# PSU_VCC2V5_Buck.net
KiCad netlist of a schematic drawn in Altium Designer
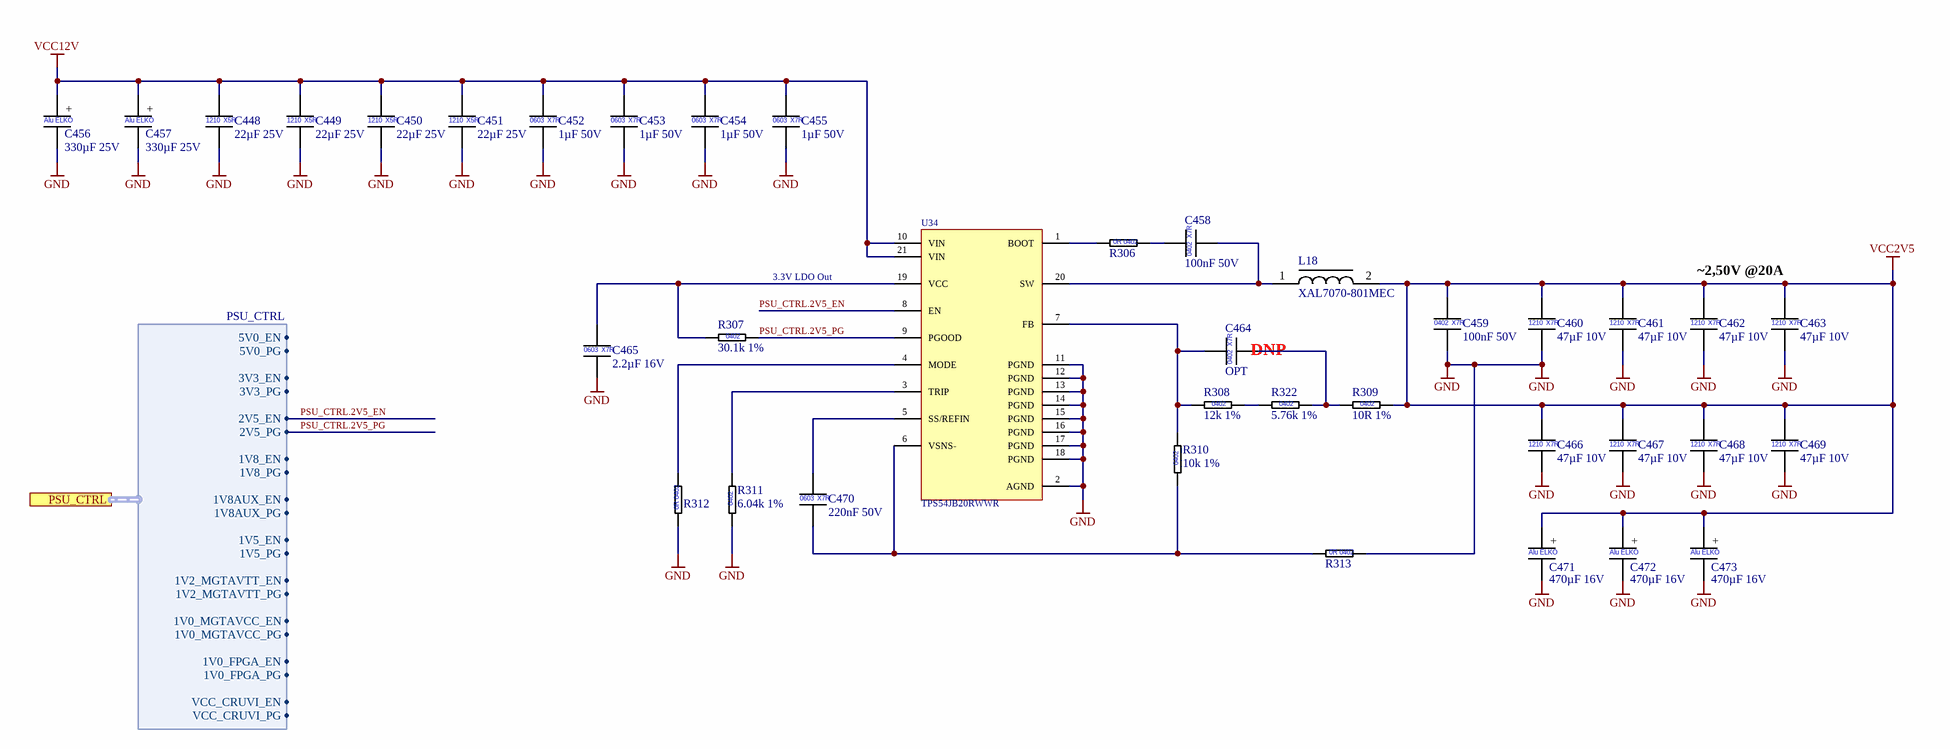
[diagram p0: PSU_VCC2V5_Buck.SchDoc]

(export (version "E")
  (design (tool "Eeschema 10.0.6"))
  (components
    (comp (ref "C448")
      (value "22µF 25V")
      (footprint "Cap:CAP_1210")
      (description "Multilayer Ceramic Capacitors MLCC - SMD/SMT 1210 25VDC")
      (libsource (lib "Cap") (part "CAP_1210_22µF_25V"))
    )
    (comp (ref "C449")
      (value "22µF 25V")
      (footprint "Cap:CAP_1210")
      (description "Multilayer Ceramic Capacitors MLCC - SMD/SMT 1210 25VDC")
      (libsource (lib "Cap") (part "CAP_1210_22µF_25V"))
    )
    (comp (ref "C450")
      (value "22µF 25V")
      (footprint "Cap:CAP_1210")
      (description "Multilayer Ceramic Capacitors MLCC - SMD/SMT 1210 25VDC")
      (libsource (lib "Cap") (part "CAP_1210_22µF_25V"))
    )
    (comp (ref "C451")
      (value "22µF 25V")
      (footprint "Cap:CAP_1210")
      (description "Multilayer Ceramic Capacitors MLCC - SMD/SMT 1210 25VDC")
      (libsource (lib "Cap") (part "CAP_1210_22µF_25V"))
    )
    (comp (ref "C452")
      (value "1µF 50V")
      (footprint "CAP_0603")
      (description "Multilayer Ceramic Capacitors MLCC - SMD/SMT 50V 1uF X7R 0603 10%")
      (libsource (lib "Cap") (part "CAP_0603_1µF_50V_X7R_10%"))
    )
    (comp (ref "C453")
      (value "1µF 50V")
      (footprint "CAP_0603")
      (description "Multilayer Ceramic Capacitors MLCC - SMD/SMT 50V 1uF X7R 0603 10%")
      (libsource (lib "Cap") (part "CAP_0603_1µF_50V_X7R_10%"))
    )
    (comp (ref "C454")
      (value "1µF 50V")
      (footprint "CAP_0603")
      (description "Multilayer Ceramic Capacitors MLCC - SMD/SMT 50V 1uF X7R 0603 10%")
      (libsource (lib "Cap") (part "CAP_0603_1µF_50V_X7R_10%"))
    )
    (comp (ref "C455")
      (value "1µF 50V")
      (footprint "CAP_0603")
      (description "Multilayer Ceramic Capacitors MLCC - SMD/SMT 50V 1uF X7R 0603 10%")
      (libsource (lib "Cap") (part "CAP_0603_1µF_50V_X7R_10%"))
    )
    (comp (ref "C456")
      (value "330µF 25V")
      (footprint "Cap:WCAP-PTG5_D10H12.5")
      (description "Organische Polymer-Aluminiumkondensatoren 330uF 25 Volts 20% AEC-Q200")
      (libsource (lib "Cap") (part "CAP_D10L12.5_330µF_25V"))
    )
    (comp (ref "C457")
      (value "330µF 25V")
      (footprint "Cap:WCAP-PTG5_D10H12.5")
      (description "Organische Polymer-Aluminiumkondensatoren 330uF 25 Volts 20% AEC-Q200")
      (libsource (lib "Cap") (part "CAP_D10L12.5_330µF_25V"))
    )
    (comp (ref "C458")
      (value "100nF 50V")
      (footprint "Cap:CAP_0402")
      (description "Multilayer Ceramic Capacitors MLCC - SMD/SMT 0402 50VDC")
      (libsource (lib "") (part "CAP_0402_100nF_50V_1"))
    )
    (comp (ref "C459")
      (value "100nF 50V")
      (footprint "Cap:CAP_0402")
      (description "Multilayer Ceramic Capacitors MLCC - SMD/SMT 0402 50VDC")
      (libsource (lib "Cap") (part "CAP_0402_100nF_50V"))
    )
    (comp (ref "C460")
      (value "47µF 10V")
      (footprint "Cap:CAP_1210")
      (description "Multilayer Ceramic Capacitors MLCC - SMD/SMT 47 uF 10 VDC 10% 1210 X7R")
      (libsource (lib "Cap") (part "CAP_1210_47µF_10V_X7R_10%"))
    )
    (comp (ref "C461")
      (value "47µF 10V")
      (footprint "Cap:CAP_1210")
      (description "Multilayer Ceramic Capacitors MLCC - SMD/SMT 47 uF 10 VDC 10% 1210 X7R")
      (libsource (lib "Cap") (part "CAP_1210_47µF_10V_X7R_10%"))
    )
    (comp (ref "C462")
      (value "47µF 10V")
      (footprint "Cap:CAP_1210")
      (description "Multilayer Ceramic Capacitors MLCC - SMD/SMT 47 uF 10 VDC 10% 1210 X7R")
      (libsource (lib "Cap") (part "CAP_1210_47µF_10V_X7R_10%"))
    )
    (comp (ref "C463")
      (value "47µF 10V")
      (footprint "Cap:CAP_1210")
      (description "Multilayer Ceramic Capacitors MLCC - SMD/SMT 47 uF 10 VDC 10% 1210 X7R")
      (libsource (lib "Cap") (part "CAP_1210_47µF_10V_X7R_10%"))
    )
    (comp (ref "C464")
      (value "OPT")
      (footprint "Cap:CAP_0402")
      (description "Multilayer Ceramic Capacitors MLCC - SMD/SMT 0402 Optional Placeholder")
      (libsource (lib "Cap") (part "CAP_0402_OPT"))
    )
    (comp (ref "C465")
      (value "2.2µF 16V")
      (footprint "Cap:CAP_0603")
      (description "Multilayer Ceramic Capacitors MLCC - SMD/SMT 2.2 uF 16 VDC 10% 0603 X7R")
      (libsource (lib "Cap") (part "CAP_0603_2.2µF_16V_X7R_10%"))
    )
    (comp (ref "C466")
      (value "47µF 10V")
      (footprint "Cap:CAP_1210")
      (description "Multilayer Ceramic Capacitors MLCC - SMD/SMT 47 uF 10 VDC 10% 1210 X7R")
      (libsource (lib "Cap") (part "CAP_1210_47µF_10V_X7R_10%"))
    )
    (comp (ref "C467")
      (value "47µF 10V")
      (footprint "Cap:CAP_1210")
      (description "Multilayer Ceramic Capacitors MLCC - SMD/SMT 47 uF 10 VDC 10% 1210 X7R")
      (libsource (lib "Cap") (part "CAP_1210_47µF_10V_X7R_10%"))
    )
    (comp (ref "C468")
      (value "47µF 10V")
      (footprint "Cap:CAP_1210")
      (description "Multilayer Ceramic Capacitors MLCC - SMD/SMT 47 uF 10 VDC 10% 1210 X7R")
      (libsource (lib "Cap") (part "CAP_1210_47µF_10V_X7R_10%"))
    )
    (comp (ref "C469")
      (value "47µF 10V")
      (footprint "Cap:CAP_1210")
      (description "Multilayer Ceramic Capacitors MLCC - SMD/SMT 47 uF 10 VDC 10% 1210 X7R")
      (libsource (lib "Cap") (part "CAP_1210_47µF_10V_X7R_10%"))
    )
    (comp (ref "C470")
      (value "220nF 50V")
      (footprint "CAP_0603")
      (description "Multilayer Ceramic Capacitors MLCC - SMD/SMT 0.22 uF 50 VDC 10% 0603 X7R")
      (libsource (lib "Cap") (part "CAP_0603_220nF_50V_X7R_10%"))
    )
    (comp (ref "C471")
      (value "470µF 16V")
      (footprint "Cap:WCAP-PTG5_D8H13")
      (description "Organische Polymer-Aluminiumkondensatoren 470uF 16 Volts 20%")
      (libsource (lib "Cap") (part "CAP_D8L9_470µF_16V"))
    )
    (comp (ref "C472")
      (value "470µF 16V")
      (footprint "Cap:WCAP-PTG5_D8H13")
      (description "Organische Polymer-Aluminiumkondensatoren 470uF 16 Volts 20%")
      (libsource (lib "Cap") (part "CAP_D8L9_470µF_16V"))
    )
    (comp (ref "C473")
      (value "470µF 16V")
      (footprint "Cap:WCAP-PTG5_D8H13")
      (description "Organische Polymer-Aluminiumkondensatoren 470uF 16 Volts 20%")
      (libsource (lib "Cap") (part "CAP_D8L9_470µF_16V"))
    )
    (comp (ref "L18")
      (value "XAL7070-801MEC")
      (footprint "indc:COILCRAFT_XAL7070")
      (description "Power Inductors - SMD 800nH Shld 20% 25.8A 2.29mOhms AECQ200")
      (libsource (lib "Indc") (part "XAL7070-801MEC_Power Inductors SMD 800nH Shld 20% 25.8A 2.29mOhms AECQ200"))
    )
    (comp (ref "R306")
      (value "0R Jumper")
      (footprint "res:RES_0402")
      (description "Thick Film Resistors - SMD 0Ohm")
      (libsource (lib "Res") (part "RES_0402_0R Jumper"))
    )
    (comp (ref "R307")
      (value "30.1k 1%")
      (footprint "res:RES_0402")
      (description "Thick Film Resistors - SMD 30.1kOhm 1%")
      (libsource (lib "Res") (part "RES_0402_30.1k_1%"))
    )
    (comp (ref "R308")
      (value "12k 1%")
      (footprint "res:RES_0402")
      (description "Thick Film Resistors - SMD 12kOhm 1%")
      (libsource (lib "Res") (part "RES_0402_12k_1%"))
    )
    (comp (ref "R309")
      (value "10R 1%")
      (footprint "res:RES_0402")
      (description "Thick Film Resistors - SMD 10Ohm 1%")
      (libsource (lib "Res") (part "RES_0402_10R_1%"))
    )
    (comp (ref "R310")
      (value "10k 1%")
      (footprint "Res:RES_0402")
      (description "Thick Film Resistors - SMD 10kOhm 1%")
      (libsource (lib "Res") (part "RES_0402_10k_1%"))
    )
    (comp (ref "R311")
      (value "6.04k 1%")
      (footprint "Res:RES_0402")
      (description "Thick Film Resistors - SMD 6.04kOhm 1%")
      (libsource (lib "Res") (part "RES_0402_6.04k_1%"))
    )
    (comp (ref "R312")
      (value "0R Jumper")
      (footprint "res:RES_0402")
      (description "Thick Film Resistors - SMD 0Ohm")
      (libsource (lib "Res") (part "RES_0402_0R Jumper"))
    )
    (comp (ref "R313")
      (value "0R Jumper")
      (footprint "res:RES_0402")
      (description "Thick Film Resistors - SMD 0Ohm")
      (libsource (lib "Res") (part "RES_0402_0R Jumper"))
    )
    (comp (ref "R322")
      (value "5.76k 1%")
      (footprint "res:RES_0402")
      (description "Thick Film Resistors - SMD 5.76kOhm 1%")
      (libsource (lib "Res") (part "RES_0402_5.76k_1%"))
    )
    (comp (ref "U34")
      (value "TPS54JB20RWWR")
      (footprint "power:VQFN-HR21_RWW0021A")
      (description "Switching Voltage Regulators 2.7-V to 16-V input 20-A synchronous Buck")
      (libsource (lib "Power") (part "TPS54JB20RWWR_Switching Voltage Regulators 2.7-V to 16-V input 20-A synchronous Buck"))
    )
  )
  (nets
    (net (code "2") (name "/PSU_CTRL.2V5_EN") (class "Default")
      (node (ref "U34") (pin "8") (pinfunction "EN_8") (pintype "passive"))
    )
    (net (code "3") (name "/PSU_CTRL.2V5_PG") (class "Default")
      (node (ref "R307") (pin "2") (pinfunction "2_2") (pintype "passive"))
      (node (ref "U34") (pin "9") (pinfunction "PGOOD_9") (pintype "passive"))
    )
    (net (code "5") (name "GND") (class "Default")
      (node (ref "C448") (pin "2") (pinfunction "2_2") (pintype "passive"))
      (node (ref "C449") (pin "2") (pinfunction "2_2") (pintype "passive"))
      (node (ref "C450") (pin "2") (pinfunction "2_2") (pintype "passive"))
      (node (ref "C451") (pin "2") (pinfunction "2_2") (pintype "passive"))
      (node (ref "C452") (pin "2") (pinfunction "2_2") (pintype "passive"))
      (node (ref "C453") (pin "2") (pinfunction "2_2") (pintype "passive"))
      (node (ref "C454") (pin "2") (pinfunction "2_2") (pintype "passive"))
      (node (ref "C455") (pin "2") (pinfunction "2_2") (pintype "passive"))
      (node (ref "C456") (pin "2") (pinfunction "2_2") (pintype "passive"))
      (node (ref "C457") (pin "2") (pinfunction "2_2") (pintype "passive"))
      (node (ref "C459") (pin "2") (pinfunction "2_2") (pintype "passive"))
      (node (ref "C460") (pin "2") (pinfunction "2_2") (pintype "passive"))
      (node (ref "C461") (pin "2") (pinfunction "2_2") (pintype "passive"))
      (node (ref "C462") (pin "2") (pinfunction "2_2") (pintype "passive"))
      (node (ref "C463") (pin "2") (pinfunction "2_2") (pintype "passive"))
      (node (ref "C465") (pin "2") (pinfunction "2_2") (pintype "passive"))
      (node (ref "C466") (pin "2") (pinfunction "2_2") (pintype "passive"))
      (node (ref "C467") (pin "2") (pinfunction "2_2") (pintype "passive"))
      (node (ref "C468") (pin "2") (pinfunction "2_2") (pintype "passive"))
      (node (ref "C469") (pin "2") (pinfunction "2_2") (pintype "passive"))
      (node (ref "C471") (pin "2") (pinfunction "2_2") (pintype "passive"))
      (node (ref "C472") (pin "2") (pinfunction "2_2") (pintype "passive"))
      (node (ref "C473") (pin "2") (pinfunction "2_2") (pintype "passive"))
      (node (ref "R311") (pin "1") (pinfunction "1_1") (pintype "passive"))
      (node (ref "R312") (pin "1") (pinfunction "1_1") (pintype "passive"))
      (node (ref "R313") (pin "2") (pinfunction "2_2") (pintype "passive"))
      (node (ref "U34") (pin "11") (pinfunction "PGND_11") (pintype "passive"))
      (node (ref "U34") (pin "12") (pinfunction "PGND_12") (pintype "passive"))
      (node (ref "U34") (pin "13") (pinfunction "PGND_13") (pintype "passive"))
      (node (ref "U34") (pin "14") (pinfunction "PGND_14") (pintype "passive"))
      (node (ref "U34") (pin "15") (pinfunction "PGND_15") (pintype "passive"))
      (node (ref "U34") (pin "16") (pinfunction "PGND_16") (pintype "passive"))
      (node (ref "U34") (pin "17") (pinfunction "PGND_17") (pintype "passive"))
      (node (ref "U34") (pin "18") (pinfunction "PGND_18") (pintype "passive"))
      (node (ref "U34") (pin "2") (pinfunction "AGND_2") (pintype "passive"))
    )
    (net (code "6") (name "Net-(C458-Pad1)") (class "Default")
      (node (ref "C458") (pin "1") (pinfunction "1_1") (pintype "passive"))
      (node (ref "R306") (pin "2") (pinfunction "2_2") (pintype "passive"))
    )
    (net (code "7") (name "Net-(C464-Pad2)") (class "Default")
      (node (ref "C464") (pin "2") (pinfunction "2_2") (pintype "passive"))
      (node (ref "R309") (pin "1") (pinfunction "1_1") (pintype "passive"))
      (node (ref "R322") (pin "2") (pinfunction "2_2") (pintype "passive"))
    )
    (net (code "8") (name "Net-(R308-Pad2)") (class "Default")
      (node (ref "R308") (pin "2") (pinfunction "2_2") (pintype "passive"))
      (node (ref "R322") (pin "1") (pinfunction "1_1") (pintype "passive"))
    )
    (net (code "9") (name "Net-(U34-BOOT)") (class "Default")
      (node (ref "R306") (pin "1") (pinfunction "1_1") (pintype "passive"))
      (node (ref "U34") (pin "1") (pinfunction "BOOT_1") (pintype "passive"))
    )
    (net (code "10") (name "Net-(U34-FB)") (class "Default")
      (node (ref "C464") (pin "1") (pinfunction "1_1") (pintype "passive"))
      (node (ref "R308") (pin "1") (pinfunction "1_1") (pintype "passive"))
      (node (ref "R310") (pin "2") (pinfunction "2_2") (pintype "passive"))
      (node (ref "U34") (pin "7") (pinfunction "FB_7") (pintype "passive"))
    )
    (net (code "11") (name "Net-(U34-MODE)") (class "Default")
      (node (ref "R312") (pin "2") (pinfunction "2_2") (pintype "passive"))
      (node (ref "U34") (pin "4") (pinfunction "MODE_4") (pintype "passive"))
    )
    (net (code "12") (name "Net-(U34-SS{slash}REFIN)") (class "Default")
      (node (ref "C470") (pin "1") (pinfunction "1_1") (pintype "passive"))
      (node (ref "U34") (pin "5") (pinfunction "SS/REFIN_5") (pintype "passive"))
    )
    (net (code "13") (name "Net-(U34-SW)") (class "Default")
      (node (ref "C458") (pin "2") (pinfunction "2_2") (pintype "passive"))
      (node (ref "L18") (pin "1") (pinfunction "1_1") (pintype "passive"))
      (node (ref "U34") (pin "20") (pinfunction "SW_20") (pintype "passive"))
    )
    (net (code "14") (name "Net-(U34-TRIP)") (class "Default")
      (node (ref "R311") (pin "2") (pinfunction "2_2") (pintype "passive"))
      (node (ref "U34") (pin "3") (pinfunction "TRIP_3") (pintype "passive"))
    )
    (net (code "15") (name "Net-(U34-VCC)") (class "Default")
      (node (ref "C465") (pin "1") (pinfunction "1_1") (pintype "passive"))
      (node (ref "R307") (pin "1") (pinfunction "1_1") (pintype "passive"))
      (node (ref "U34") (pin "19") (pinfunction "VCC_19") (pintype "passive"))
    )
    (net (code "16") (name "Net-(U34-VSNS-)") (class "Default")
      (node (ref "C470") (pin "2") (pinfunction "2_2") (pintype "passive"))
      (node (ref "R310") (pin "1") (pinfunction "1_1") (pintype "passive"))
      (node (ref "R313") (pin "1") (pinfunction "1_1") (pintype "passive"))
      (node (ref "U34") (pin "6") (pinfunction "VSNS-_6") (pintype "passive"))
    )
    (net (code "17") (name "VCC2V5") (class "Default")
      (node (ref "C459") (pin "1") (pinfunction "1_1") (pintype "passive"))
      (node (ref "C460") (pin "1") (pinfunction "1_1") (pintype "passive"))
      (node (ref "C461") (pin "1") (pinfunction "1_1") (pintype "passive"))
      (node (ref "C462") (pin "1") (pinfunction "1_1") (pintype "passive"))
      (node (ref "C463") (pin "1") (pinfunction "1_1") (pintype "passive"))
      (node (ref "C466") (pin "1") (pinfunction "1_1") (pintype "passive"))
      (node (ref "C467") (pin "1") (pinfunction "1_1") (pintype "passive"))
      (node (ref "C468") (pin "1") (pinfunction "1_1") (pintype "passive"))
      (node (ref "C469") (pin "1") (pinfunction "1_1") (pintype "passive"))
      (node (ref "C471") (pin "1") (pinfunction "1_1") (pintype "passive"))
      (node (ref "C472") (pin "1") (pinfunction "1_1") (pintype "passive"))
      (node (ref "C473") (pin "1") (pinfunction "1_1") (pintype "passive"))
      (node (ref "L18") (pin "2") (pinfunction "2_2") (pintype "passive"))
      (node (ref "R309") (pin "2") (pinfunction "2_2") (pintype "passive"))
    )
    (net (code "18") (name "VCC12V") (class "Default")
      (node (ref "C448") (pin "1") (pinfunction "1_1") (pintype "passive"))
      (node (ref "C449") (pin "1") (pinfunction "1_1") (pintype "passive"))
      (node (ref "C450") (pin "1") (pinfunction "1_1") (pintype "passive"))
      (node (ref "C451") (pin "1") (pinfunction "1_1") (pintype "passive"))
      (node (ref "C452") (pin "1") (pinfunction "1_1") (pintype "passive"))
      (node (ref "C453") (pin "1") (pinfunction "1_1") (pintype "passive"))
      (node (ref "C454") (pin "1") (pinfunction "1_1") (pintype "passive"))
      (node (ref "C455") (pin "1") (pinfunction "1_1") (pintype "passive"))
      (node (ref "C456") (pin "1") (pinfunction "1_1") (pintype "passive"))
      (node (ref "C457") (pin "1") (pinfunction "1_1") (pintype "passive"))
      (node (ref "U34") (pin "10") (pinfunction "VIN_10") (pintype "passive"))
      (node (ref "U34") (pin "21") (pinfunction "VIN_21") (pintype "passive"))
    )
  )
)
